# 09_Misc.net
KiCad netlist of a schematic drawn in Altium Designer
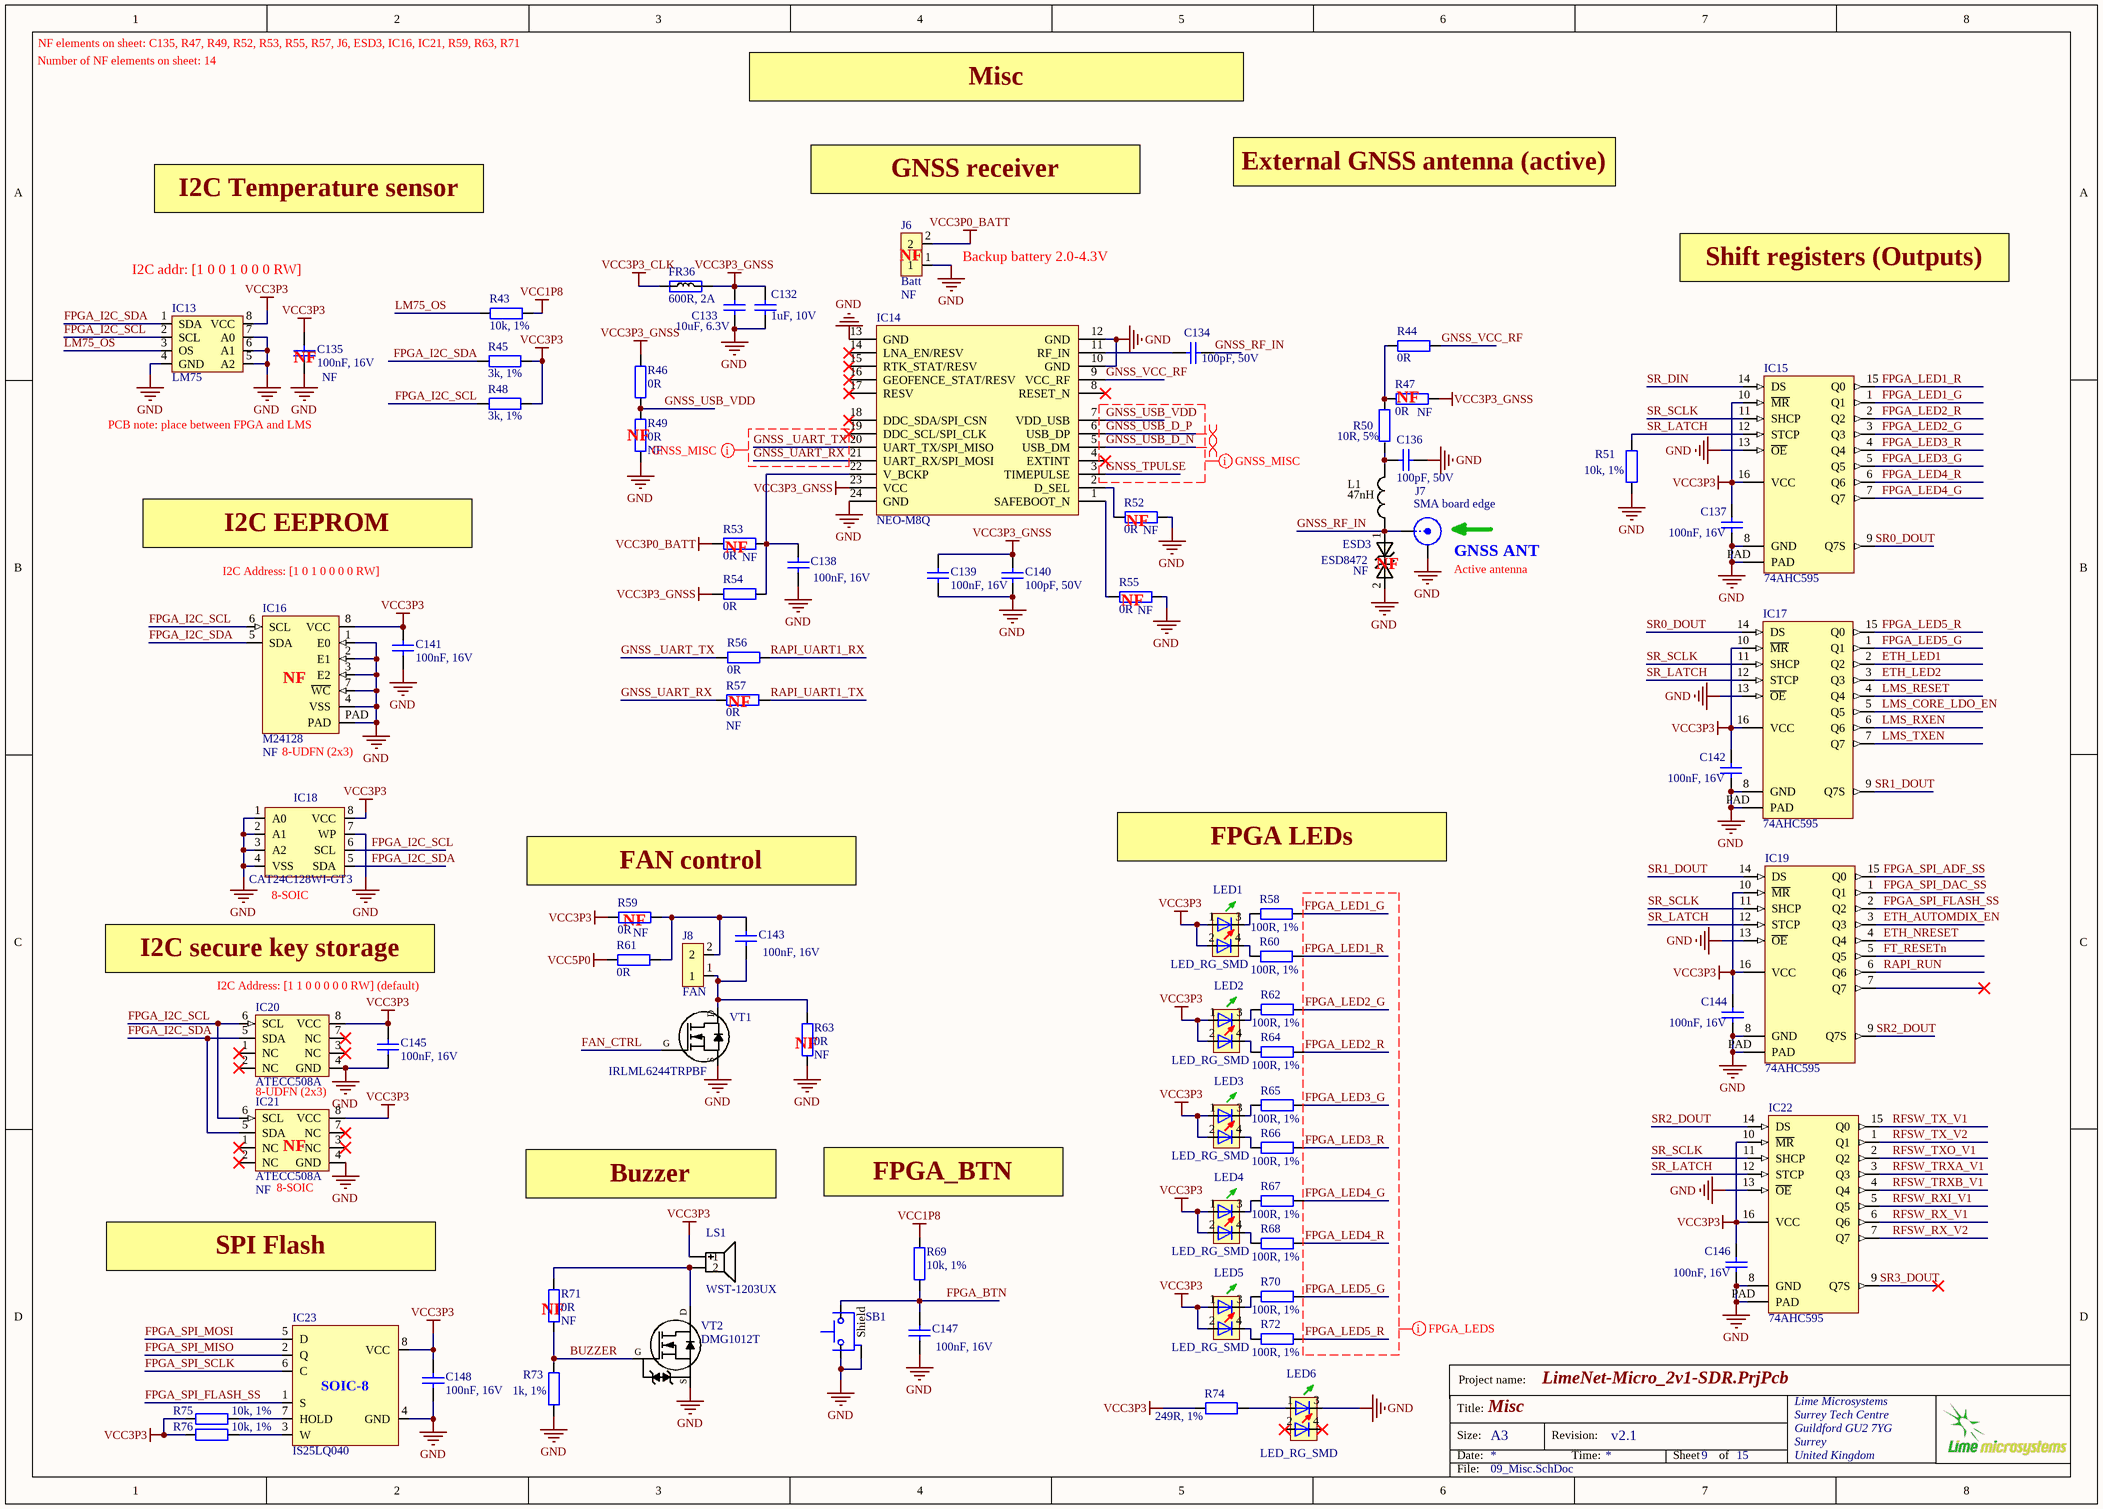
[diagram p0: 09_Misc.SchDoc]

(export (version "E")
  (design (tool "Eeschema 10.0.6"))
  (components
    (comp (ref "C132")
      (value "1uF, 10V")
      (footprint "CAP0402")
      (description "CAP CER 1UF 10V X5R 0402")
      (fields (field (name "MANUFACTURER") "Yageo") (field (name "TOLERANCE") "±20%"))
      (libsource (lib "LimeMicroAltiumLib_schLib") (part "Cap_0402"))
    )
    (comp (ref "C133")
      (value "10uF, 6.3V")
      (footprint "CAP0603")
      (fields (field (name "TOLERANCE") "±20%") (field (name "MANUFACTURER") "Yageo"))
      (libsource (lib "LimeFPGAboard_schLib") (part "Cap_0603"))
    )
    (comp (ref "C134")
      (value "100pF, 50V")
      (footprint "CAP0402")
      (fields (field (name "TOLERANCE") "±5%") (field (name "MANUFACTURER") "Yageo"))
      (libsource (lib "LimeMicroAltiumLib_schLib") (part "Cap_0402"))
    )
    (comp (ref "C135")
      (value "100nF, 16V")
      (footprint "CAP0402")
      (fields
        (field (name "TOLERANCE") "10 %")
        (field (name "MANUFACTURER") "Murata Electronics")
        (field (name "MANUFACTURER PART NUMBER") "GRM155R71C104KA88D")
        (field (name "ASSEMBLY INFO") "NF")
      )
      (libsource (lib "LimeFPGAboard_schLib") (part "Cap_0603"))
    )
    (comp (ref "C136")
      (value "100pF, 50V")
      (footprint "CAP0402")
      (fields (field (name "TOLERANCE") "±5%") (field (name "MANUFACTURER") "Yageo"))
      (libsource (lib "LimeMicroAltiumLib_schLib") (part "Cap_0402"))
    )
    (comp (ref "C137")
      (value "100nF, 16V")
      (footprint "CAP0402")
      (fields
        (field (name "MANUFACTURER") "Murata Electronics")
        (field (name "TOLERANCE") "10 %")
        (field (name "MANUFACTURER PART NUMBER") "GRM155R71C104KA88D")
      )
      (libsource (lib "LimeMicroAltiumLib_schLib") (part "Cap_0402"))
    )
    (comp (ref "C138")
      (value "100nF, 16V")
      (footprint "CAP0402")
      (fields
        (field (name "TOLERANCE") "10 %")
        (field (name "MANUFACTURER") "Murata Electronics")
        (field (name "MANUFACTURER PART NUMBER") "GRM155R71C104KA88D")
      )
      (libsource (lib "LimeFPGAboard_schLib") (part "Cap_0603"))
    )
    (comp (ref "C139")
      (value "100nF, 16V")
      (footprint "CAP0402")
      (fields
        (field (name "MANUFACTURER") "Murata Electronics")
        (field (name "TOLERANCE") "10 %")
        (field (name "MANUFACTURER PART NUMBER") "GRM155R71C104KA88D")
      )
      (libsource (lib "LimeMicroAltiumLib_schLib") (part "Cap_0402"))
    )
    (comp (ref "C140")
      (value "100pF, 50V")
      (footprint "CAP0402")
      (fields (field (name "TOLERANCE") "±5%") (field (name "MANUFACTURER") "Yageo"))
      (libsource (lib "LimeMicroAltiumLib_schLib") (part "Cap_0402"))
    )
    (comp (ref "C141")
      (value "100nF, 16V")
      (footprint "CAP0402")
      (fields
        (field (name "TOLERANCE") "10 %")
        (field (name "MANUFACTURER") "Murata Electronics")
        (field (name "MANUFACTURER PART NUMBER") "GRM155R71C104KA88D")
      )
      (libsource (lib "LimeFPGAboard_schLib") (part "Cap_0603"))
    )
    (comp (ref "C142")
      (value "100nF, 16V")
      (footprint "CAP0402")
      (fields
        (field (name "MANUFACTURER") "Murata Electronics")
        (field (name "TOLERANCE") "10 %")
        (field (name "MANUFACTURER PART NUMBER") "GRM155R71C104KA88D")
      )
      (libsource (lib "LimeMicroAltiumLib_schLib") (part "Cap_0402"))
    )
    (comp (ref "C143")
      (value "100nF, 16V")
      (footprint "CAP0402")
      (fields
        (field (name "TOLERANCE") "10 %")
        (field (name "MANUFACTURER") "Murata Electronics")
        (field (name "MANUFACTURER PART NUMBER") "GRM155R71C104KA88D")
      )
      (libsource (lib "LimeFPGAboard_schLib") (part "Cap_0603"))
    )
    (comp (ref "C144")
      (value "100nF, 16V")
      (footprint "CAP0402")
      (fields
        (field (name "MANUFACTURER") "Murata Electronics")
        (field (name "TOLERANCE") "10 %")
        (field (name "MANUFACTURER PART NUMBER") "GRM155R71C104KA88D")
      )
      (libsource (lib "LimeMicroAltiumLib_schLib") (part "Cap_0402"))
    )
    (comp (ref "C145")
      (value "100nF, 16V")
      (footprint "CAP0402")
      (fields
        (field (name "TOLERANCE") "10 %")
        (field (name "MANUFACTURER") "Murata Electronics")
        (field (name "MANUFACTURER PART NUMBER") "GRM155R71C104KA88D")
      )
      (libsource (lib "LimeFPGAboard_schLib") (part "Cap_0603"))
    )
    (comp (ref "C146")
      (value "100nF, 16V")
      (footprint "CAP0402")
      (fields
        (field (name "MANUFACTURER") "Murata Electronics")
        (field (name "TOLERANCE") "10 %")
        (field (name "MANUFACTURER PART NUMBER") "GRM155R71C104KA88D")
      )
      (libsource (lib "LimeMicroAltiumLib_schLib") (part "Cap_0402"))
    )
    (comp (ref "C147")
      (value "100nF, 16V")
      (footprint "CAP0402")
      (fields
        (field (name "TOLERANCE") "10 %")
        (field (name "MANUFACTURER") "Murata Electronics")
        (field (name "MANUFACTURER PART NUMBER") "GRM155R71C104KA88D")
      )
      (libsource (lib "LimeFPGAboard_schLib") (part "Cap_0603"))
    )
    (comp (ref "C148")
      (value "100nF, 16V")
      (footprint "CAP0402")
      (fields
        (field (name "TOLERANCE") "10 %")
        (field (name "MANUFACTURER") "Murata Electronics")
        (field (name "MANUFACTURER PART NUMBER") "GRM155R71C104KA88D")
      )
      (libsource (lib "LimeFPGAboard_schLib") (part "Cap_0603"))
    )
    (comp (ref "ESD3")
      (value "ESD8472")
      (footprint "ESD8472_X3DFN2")
      (fields (field (name "MANUFACTURER") "ON Semiconductor") (field (name "ASSEMBLY INFO") "NF"))
      (libsource (lib "LimeMicroAltiumLib_schLib") (part "ESD8472"))
    )
    (comp (ref "FR36")
      (value "600R, 2A")
      (footprint "RES0805")
      (fields (field (name "MANUFACTURER") "TDK Corporation"))
      (libsource (lib "LimeFPGAboard_schLib") (part "Ferrite"))
    )
    (comp (ref "IC13")
      (value "LM75")
      (footprint "HWSON8_LM75")
      (fields (field (name "MANUFACTURER") "NXP Semiconductors"))
      (libsource (lib "LimeMicroAltiumLib_schLib") (part "LM75"))
    )
    (comp (ref "IC14")
      (value "NEO-M8Q")
      (footprint "NEO-7M/8M")
      (description "GNSS engine for GPS/QZSS, GLONASS")
      (fields (field (name "MANUFACTURER") "u-blox") (field (name "MANUFACTURER PART NUMBER") "NEO-M8Q-0"))
      (libsource (lib "LimeMicroAltiumLib_schLib") (part "NEO-M8P_M8M"))
    )
    (comp (ref "IC15")
      (value "74AHC595")
      (footprint "74HC595BQ,115")
      (fields (field (name "MANUFACTURER") "Nexperia USA Inc."))
      (libsource (lib "LimeMicroAltiumLib_schLib") (part "74HC595BQ,115"))
    )
    (comp (ref "IC16")
      (value "M24128")
      (footprint "M24128-DFMC6TG")
      (fields (field (name "MANUFACTURER") "STMicroelectronics") (field (name "ASSEMBLY INFO") "NF"))
      (libsource (lib "LimeMicroAltiumLib_schLib") (part "M24128-DFMC6TG"))
    )
    (comp (ref "IC17")
      (value "74AHC595")
      (footprint "74HC595BQ,115")
      (fields (field (name "MANUFACTURER") "Nexperia USA Inc."))
      (libsource (lib "LimeMicroAltiumLib_schLib") (part "74HC595BQ,115"))
    )
    (comp (ref "IC18")
      (value "CAT24C128WI-GT3")
      (footprint "SOIC127P600-8DL_v2")
      (fields (field (name "MANUFACTURER") "ON Semiconductor") (field (name "BASE PART NUMBER") "CAT24C128"))
      (libsource (lib "LimeMicroAltiumLib_schLib") (part "24FC64F"))
    )
    (comp (ref "IC19")
      (value "74AHC595")
      (footprint "74HC595BQ,115")
      (fields (field (name "MANUFACTURER") "Nexperia USA Inc."))
      (libsource (lib "LimeMicroAltiumLib_schLib") (part "74HC595BQ,115"))
    )
    (comp (ref "IC20")
      (value "ATECC508A")
      (footprint "ATECC508A_UDFN8")
      (fields (field (name "MANUFACTURER") "Microchip"))
      (libsource (lib "LimeMicroAltiumLib_schLib_r01") (part "ATECC508A_authentication_IC"))
    )
    (comp (ref "IC21")
      (value "ATECC508A")
      (footprint "SOIC127P600-8DL_v2")
      (fields
        (field (name "ASSEMBLY INFO") "NF")
        (field (name "MANUFACTURER") "Microchip Technology")
        (field (name "BASE PART NUMBER") "ATECC508")
      )
      (libsource (lib "LimeMicroAltiumLib_schLib_r01") (part "ATECC508A_authentication_IC"))
    )
    (comp (ref "IC22")
      (value "74AHC595")
      (footprint "74HC595BQ,115")
      (fields (field (name "MANUFACTURER") "Nexperia USA Inc."))
      (libsource (lib "LimeMicroAltiumLib_schLib") (part "74HC595BQ,115"))
    )
    (comp (ref "IC23")
      (value "IS25LQ040")
      (footprint "M25P40-VMN6TPB_SO8N")
      (fields (field (name "MANUFACTURER") "ISSI, Integrated Silicon Solution Inc"))
      (libsource (lib "LimeFPGAboard_schLib") (part "M25P40"))
    )
    (comp (ref "J6")
      (value "Batt")
      (footprint "HDR_1x2")
      (fields (field (name "ASSEMBLY INFO") "NF") (field (name "MANUFACTURER") "3M"))
      (libsource (lib "LimeFPGAboard_schLib") (part "Jumper"))
    )
    (comp (ref "J7")
      (value "SMA board edge")
      (footprint "SMA_connector_board_edge_SM")
      (description "CONN SMA JACK STR 50OHM EDGE MNT")
      (fields (field (name "MANUFACTURER") "RF Solutions"))
      (libsource (lib "LimeMicroAltiumLib_schLib") (part "RF_IF_connector"))
    )
    (comp (ref "J8")
      (value "FAN")
      (footprint "HDR_1x2")
      (fields (field (name "MANUFACTURER") "3M"))
      (libsource (lib "LimeFPGAboard_schLib") (part "Jumper"))
    )
    (comp (ref "L1")
      (value "47nH")
      (footprint "RES0402")
      (fields
        (field (name "MANUFACTURER") "COILCRAFT")
        (field (name "MANUFACTURER PART NUMBER") "0402HP-47NXJLU")
      )
      (libsource (lib "LimeMicroAltiumLib_schLib") (part "Inductor_0603"))
    )
    (comp (ref "LED1")
      (value "LED_RG_SMD")
      (footprint "LED-2x0603")
      (fields (field (name "MANUFACTURER") "Avago Technologies US Inc."))
      (libsource (lib "LimeMicroAltiumLib_schLib") (part "LED_green_red_SMD"))
    )
    (comp (ref "LED2")
      (value "LED_RG_SMD")
      (footprint "LED-2x0603")
      (fields (field (name "MANUFACTURER") "Avago Technologies US Inc."))
      (libsource (lib "LimeMicroAltiumLib_schLib") (part "LED_green_red_SMD"))
    )
    (comp (ref "LED3")
      (value "LED_RG_SMD")
      (footprint "LED-2x0603")
      (fields (field (name "MANUFACTURER") "Avago Technologies US Inc."))
      (libsource (lib "LimeMicroAltiumLib_schLib") (part "LED_green_red_SMD"))
    )
    (comp (ref "LED4")
      (value "LED_RG_SMD")
      (footprint "LED-2x0603")
      (fields (field (name "MANUFACTURER") "Avago Technologies US Inc."))
      (libsource (lib "LimeMicroAltiumLib_schLib") (part "LED_green_red_SMD"))
    )
    (comp (ref "LED5")
      (value "LED_RG_SMD")
      (footprint "LED-2x0603")
      (fields (field (name "MANUFACTURER") "Avago Technologies US Inc."))
      (libsource (lib "LimeMicroAltiumLib_schLib") (part "LED_green_red_SMD"))
    )
    (comp (ref "LED6")
      (value "LED_RG_SMD")
      (footprint "LED-2x0603")
      (fields (field (name "MANUFACTURER") "Avago Technologies US Inc."))
      (libsource (lib "LimeMicroAltiumLib_schLib") (part "LED_green_red_SMD"))
    )
    (comp (ref "LS1")
      (value "WST-1203UX")
      (footprint "BUZZER_WST-1203UX")
      (fields (field (name "MANUFACTURER") "Soberton Inc."))
      (libsource (lib "LimeMicroAltiumLib_schLib_r01") (part "BUZZER_WST-1203UX"))
    )
    (comp (ref "R43")
      (value "10k, 1%")
      (footprint "RES0402")
      (fields (field (name "MANUFACTURER") "Yageo") (field (name "TOLERANCE") "±1%"))
      (libsource (lib "LimeMicroAltiumLib_schLib") (part "Res_0402"))
    )
    (comp (ref "R44")
      (value "0R")
      (footprint "RES0402")
      (fields (field (name "MANUFACTURER") "Yageo") (field (name "TOLERANCE") "Jumper"))
      (libsource (lib "LimeMicroAltiumLib_schLib") (part "Res_0402"))
    )
    (comp (ref "R45")
      (value "3k, 1%")
      (footprint "RES0402")
      (fields (field (name "TOLERANCE") "±1%") (field (name "MANUFACTURER") "Vishay Dale"))
      (libsource (lib "LimeMicroAltiumLib_schLib") (part "Res_0402"))
    )
    (comp (ref "R46")
      (value "0R")
      (footprint "RES0402")
      (fields (field (name "MANUFACTURER") "Yageo") (field (name "TOLERANCE") "Jumper"))
      (libsource (lib "LimeMicroAltiumLib_schLib") (part "Res_0402"))
    )
    (comp (ref "R47")
      (value "0R")
      (footprint "RES0402")
      (fields
        (field (name "ASSEMBLY INFO") "NF")
        (field (name "MANUFACTURER") "Yageo")
        (field (name "TOLERANCE") "Jumper")
      )
      (libsource (lib "LimeMicroAltiumLib_schLib") (part "Res_0402"))
    )
    (comp (ref "R48")
      (value "3k, 1%")
      (footprint "RES0402")
      (fields (field (name "TOLERANCE") "±1%") (field (name "MANUFACTURER") "Vishay Dale"))
      (libsource (lib "LimeMicroAltiumLib_schLib") (part "Res_0402"))
    )
    (comp (ref "R49")
      (value "0R")
      (footprint "RES0402")
      (fields
        (field (name "ASSEMBLY INFO") "NF")
        (field (name "MANUFACTURER") "Yageo")
        (field (name "TOLERANCE") "Jumper")
      )
      (libsource (lib "LimeMicroAltiumLib_schLib") (part "Res_0402"))
    )
    (comp (ref "R50")
      (value "10R, 5%")
      (footprint "RES0402")
      (fields (field (name "TOLERANCE") "±5%") (field (name "MANUFACTURER") "Yageo"))
      (libsource (lib "LimeMicroAltiumLib_schLib") (part "Res_0402"))
    )
    (comp (ref "R51")
      (value "10k, 1%")
      (footprint "RES0402")
      (fields (field (name "MANUFACTURER") "Yageo") (field (name "TOLERANCE") "±1%"))
      (libsource (lib "LimeMicroAltiumLib_schLib") (part "Res_0402"))
    )
    (comp (ref "R52")
      (value "0R")
      (footprint "RES0402")
      (fields
        (field (name "ASSEMBLY INFO") "NF")
        (field (name "MANUFACTURER") "Yageo")
        (field (name "TOLERANCE") "Jumper")
      )
      (libsource (lib "LimeMicroAltiumLib_schLib") (part "Res_0402"))
    )
    (comp (ref "R53")
      (value "0R")
      (footprint "RES0402")
      (fields
        (field (name "ASSEMBLY INFO") "NF")
        (field (name "MANUFACTURER") "Yageo")
        (field (name "TOLERANCE") "Jumper")
      )
      (libsource (lib "LimeMicroAltiumLib_schLib") (part "Res_0402"))
    )
    (comp (ref "R54")
      (value "0R")
      (footprint "RES0402")
      (fields (field (name "MANUFACTURER") "Yageo") (field (name "TOLERANCE") "Jumper"))
      (libsource (lib "LimeMicroAltiumLib_schLib") (part "Res_0402"))
    )
    (comp (ref "R55")
      (value "0R")
      (footprint "RES0402")
      (fields
        (field (name "ASSEMBLY INFO") "NF")
        (field (name "MANUFACTURER") "Yageo")
        (field (name "TOLERANCE") "Jumper")
      )
      (libsource (lib "LimeMicroAltiumLib_schLib") (part "Res_0402"))
    )
    (comp (ref "R56")
      (value "0R")
      (footprint "RES0402")
      (fields (field (name "MANUFACTURER") "Yageo") (field (name "TOLERANCE") "Jumper"))
      (libsource (lib "LimeMicroAltiumLib_schLib") (part "Res_0402"))
    )
    (comp (ref "R57")
      (value "0R")
      (footprint "RES0402")
      (fields
        (field (name "ASSEMBLY INFO") "NF")
        (field (name "MANUFACTURER") "Yageo")
        (field (name "TOLERANCE") "Jumper")
      )
      (libsource (lib "LimeMicroAltiumLib_schLib") (part "Res_0402"))
    )
    (comp (ref "R58")
      (value "100R, 1%")
      (footprint "RES0402")
      (fields (field (name "TOLERANCE") "±1%") (field (name "MANUFACTURER") "Stackpole Electronics Inc."))
      (libsource (lib "LimeMicroAltiumLib_schLib") (part "Res_0402"))
    )
    (comp (ref "R59")
      (value "0R")
      (footprint "RES0402")
      (fields
        (field (name "ASSEMBLY INFO") "NF")
        (field (name "MANUFACTURER") "Yageo")
        (field (name "TOLERANCE") "Jumper")
      )
      (libsource (lib "LimeMicroAltiumLib_schLib") (part "Res_0402"))
    )
    (comp (ref "R60")
      (value "100R, 1%")
      (footprint "RES0402")
      (fields (field (name "TOLERANCE") "±1%") (field (name "MANUFACTURER") "Stackpole Electronics Inc."))
      (libsource (lib "LimeMicroAltiumLib_schLib") (part "Res_0402"))
    )
    (comp (ref "R61")
      (value "0R")
      (footprint "RES0402")
      (fields (field (name "MANUFACTURER") "Yageo") (field (name "TOLERANCE") "Jumper"))
      (libsource (lib "LimeMicroAltiumLib_schLib") (part "Res_0402"))
    )
    (comp (ref "R62")
      (value "100R, 1%")
      (footprint "RES0402")
      (fields (field (name "TOLERANCE") "±1%") (field (name "MANUFACTURER") "Stackpole Electronics Inc."))
      (libsource (lib "LimeMicroAltiumLib_schLib") (part "Res_0402"))
    )
    (comp (ref "R63")
      (value "0R")
      (footprint "RES0402")
      (fields
        (field (name "ASSEMBLY INFO") "NF")
        (field (name "MANUFACTURER") "Yageo")
        (field (name "TOLERANCE") "Jumper")
      )
      (libsource (lib "LimeMicroAltiumLib_schLib") (part "Res_0402"))
    )
    (comp (ref "R64")
      (value "100R, 1%")
      (footprint "RES0402")
      (fields (field (name "TOLERANCE") "±1%") (field (name "MANUFACTURER") "Stackpole Electronics Inc."))
      (libsource (lib "LimeMicroAltiumLib_schLib") (part "Res_0402"))
    )
    (comp (ref "R65")
      (value "100R, 1%")
      (footprint "RES0402")
      (fields (field (name "TOLERANCE") "±1%") (field (name "MANUFACTURER") "Stackpole Electronics Inc."))
      (libsource (lib "LimeMicroAltiumLib_schLib") (part "Res_0402"))
    )
    (comp (ref "R66")
      (value "100R, 1%")
      (footprint "RES0402")
      (fields (field (name "TOLERANCE") "±1%") (field (name "MANUFACTURER") "Stackpole Electronics Inc."))
      (libsource (lib "LimeMicroAltiumLib_schLib") (part "Res_0402"))
    )
    (comp (ref "R67")
      (value "100R, 1%")
      (footprint "RES0402")
      (fields (field (name "TOLERANCE") "±1%") (field (name "MANUFACTURER") "Stackpole Electronics Inc."))
      (libsource (lib "LimeMicroAltiumLib_schLib") (part "Res_0402"))
    )
    (comp (ref "R68")
      (value "100R, 1%")
      (footprint "RES0402")
      (fields (field (name "TOLERANCE") "±1%") (field (name "MANUFACTURER") "Stackpole Electronics Inc."))
      (libsource (lib "LimeMicroAltiumLib_schLib") (part "Res_0402"))
    )
    (comp (ref "R69")
      (value "10k, 1%")
      (footprint "RES0402")
      (fields (field (name "MANUFACTURER") "Yageo") (field (name "TOLERANCE") "±1%"))
      (libsource (lib "LimeMicroAltiumLib_schLib") (part "Res_0402"))
    )
    (comp (ref "R70")
      (value "100R, 1%")
      (footprint "RES0402")
      (fields (field (name "TOLERANCE") "±1%") (field (name "MANUFACTURER") "Stackpole Electronics Inc."))
      (libsource (lib "LimeMicroAltiumLib_schLib") (part "Res_0402"))
    )
    (comp (ref "R71")
      (value "0R")
      (footprint "RES0402")
      (fields
        (field (name "ASSEMBLY INFO") "NF")
        (field (name "MANUFACTURER") "Yageo")
        (field (name "TOLERANCE") "Jumper")
      )
      (libsource (lib "LimeMicroAltiumLib_schLib") (part "Res_0402"))
    )
    (comp (ref "R72")
      (value "100R, 1%")
      (footprint "RES0402")
      (fields (field (name "TOLERANCE") "±1%") (field (name "MANUFACTURER") "Stackpole Electronics Inc."))
      (libsource (lib "LimeMicroAltiumLib_schLib") (part "Res_0402"))
    )
    (comp (ref "R73")
      (value "1k, 1%")
      (footprint "RES0402")
      (fields (field (name "MANUFACTURER") "Stackpole Electronics Inc") (field (name "TOLERANCE") "±1%"))
      (libsource (lib "LimeMicroAltiumLib_schLib") (part "Res_0402"))
    )
    (comp (ref "R74")
      (value "249R, 1%")
      (footprint "RES0402")
      (fields (field (name "MANUFACTURER") "Stackpole Electronics Inc") (field (name "TOLERANCE") "±1%"))
      (libsource (lib "LimeMicroAltiumLib_schLib") (part "Res_0402"))
    )
    (comp (ref "R75")
      (value "10k, 1%")
      (footprint "RES0402")
      (fields (field (name "MANUFACTURER") "Yageo") (field (name "TOLERANCE") "±1%"))
      (libsource (lib "LimeMicroAltiumLib_schLib") (part "Res_0402"))
    )
    (comp (ref "R76")
      (value "10k, 1%")
      (footprint "RES0402")
      (fields (field (name "MANUFACTURER") "Yageo") (field (name "TOLERANCE") "±1%"))
      (libsource (lib "LimeMicroAltiumLib_schLib") (part "Res_0402"))
    )
    (comp (ref "SB1")
      (value "Switch tactile right edge")
      (footprint "SW_TACTILE_RIGHT_EDGE")
      (fields (field (name "MANUFACTURER") "TE Connectivity ALCOSWITCH Switches"))
      (libsource (lib "LimeMicroAltiumLib_schLib_r01") (part "Button_right_edge"))
    )
    (comp (ref "VT1")
      (value "IRLML6244TRPBF")
      (footprint "SOT23-3")
      (description "NDS331N")
      (fields (field (name "MANUFACTURER") "Infineon Technologies"))
      (libsource (lib "LimeFPGAboard_schLib") (part "NDS331N"))
    )
    (comp (ref "VT2")
      (value "DMG1012T")
      (footprint "SOT523")
      (fields (field (name "MANUFACTURER") "Diodes Incorporated"))
      (libsource (lib "LimeMicroAltiumLib_schLib_r01") (part "DMG1012T"))
    )
  )
  (nets
    (net (code "1") (name "/BUZZER") (class "Default")
      (node (ref "R71") (pin "1") (pinfunction "1_1") (pintype "passive"))
      (node (ref "R73") (pin "1") (pinfunction "1_1") (pintype "passive"))
      (node (ref "VT2") (pin "G") (pinfunction "G_G") (pintype "passive"))
    )
    (net (code "2") (name "/ETH_AUTOMDIX_EN") (class "Default")
      (node (ref "IC19") (pin "3") (pinfunction "Q3_3") (pintype "output"))
    )
    (net (code "3") (name "/ETH_LED1") (class "Default")
      (node (ref "IC17") (pin "2") (pinfunction "Q2_2") (pintype "output"))
    )
    (net (code "4") (name "/ETH_LED2") (class "Default")
      (node (ref "IC17") (pin "3") (pinfunction "Q3_3") (pintype "output"))
    )
    (net (code "5") (name "/ETH_NRESET") (class "Default")
      (node (ref "IC19") (pin "4") (pinfunction "Q4_4") (pintype "output"))
    )
    (net (code "6") (name "/FAN_CTRL") (class "Default")
      (node (ref "VT1") (pin "G") (pinfunction "G_G") (pintype "passive"))
    )
    (net (code "7") (name "/FPGA_BTN") (class "Default")
      (node (ref "C147") (pin "1") (pinfunction "1_1") (pintype "passive"))
      (node (ref "R69") (pin "2") (pinfunction "2_2") (pintype "passive"))
      (node (ref "SB1") (pin "1") (pinfunction "1_1") (pintype "passive"))
    )
    (net (code "8") (name "/FPGA_I2C_SCL") (class "Default")
      (node (ref "IC13") (pin "2") (pinfunction "SCL_2") (pintype "passive"))
      (node (ref "IC16") (pin "6") (pinfunction "SCL_6") (pintype "input"))
      (node (ref "IC18") (pin "6") (pinfunction "SCL_6") (pintype "passive"))
      (node (ref "IC20") (pin "6") (pinfunction "SCL_6") (pintype "input"))
      (node (ref "IC21") (pin "6") (pinfunction "SCL_6") (pintype "input"))
      (node (ref "R48") (pin "2") (pinfunction "2_2") (pintype "passive"))
    )
    (net (code "9") (name "/FPGA_I2C_SDA") (class "Default")
      (node (ref "IC13") (pin "1") (pinfunction "SDA_1") (pintype "passive"))
      (node (ref "IC16") (pin "5") (pinfunction "SDA_5") (pintype "bidirectional"))
      (node (ref "IC18") (pin "5") (pinfunction "SDA_5") (pintype "passive"))
      (node (ref "IC20") (pin "5") (pinfunction "SDA_5") (pintype "bidirectional"))
      (node (ref "IC21") (pin "5") (pinfunction "SDA_5") (pintype "bidirectional"))
      (node (ref "R45") (pin "2") (pinfunction "2_2") (pintype "passive"))
    )
    (net (code "10") (name "/FPGA_LED1_G") (class "Default")
      (node (ref "IC15") (pin "1") (pinfunction "Q1_1") (pintype "output"))
      (node (ref "R58") (pin "2") (pinfunction "2_2") (pintype "passive"))
    )
    (net (code "11") (name "/FPGA_LED1_R") (class "Default")
      (node (ref "IC15") (pin "15") (pinfunction "Q0_15") (pintype "output"))
      (node (ref "R60") (pin "2") (pinfunction "2_2") (pintype "passive"))
    )
    (net (code "12") (name "/FPGA_LED2_G") (class "Default")
      (node (ref "IC15") (pin "3") (pinfunction "Q3_3") (pintype "output"))
      (node (ref "R62") (pin "2") (pinfunction "2_2") (pintype "passive"))
    )
    (net (code "13") (name "/FPGA_LED2_R") (class "Default")
      (node (ref "IC15") (pin "2") (pinfunction "Q2_2") (pintype "output"))
      (node (ref "R64") (pin "2") (pinfunction "2_2") (pintype "passive"))
    )
    (net (code "14") (name "/FPGA_LED3_G") (class "Default")
      (node (ref "IC15") (pin "5") (pinfunction "Q5_5") (pintype "output"))
      (node (ref "R65") (pin "2") (pinfunction "2_2") (pintype "passive"))
    )
    (net (code "15") (name "/FPGA_LED3_R") (class "Default")
      (node (ref "IC15") (pin "4") (pinfunction "Q4_4") (pintype "output"))
      (node (ref "R66") (pin "2") (pinfunction "2_2") (pintype "passive"))
    )
    (net (code "16") (name "/FPGA_LED4_G") (class "Default")
      (node (ref "IC15") (pin "7") (pinfunction "Q7_7") (pintype "output"))
      (node (ref "R67") (pin "2") (pinfunction "2_2") (pintype "passive"))
    )
    (net (code "17") (name "/FPGA_LED4_R") (class "Default")
      (node (ref "IC15") (pin "6") (pinfunction "Q6_6") (pintype "output"))
      (node (ref "R68") (pin "2") (pinfunction "2_2") (pintype "passive"))
    )
    (net (code "18") (name "/FPGA_LED5_G") (class "Default")
      (node (ref "IC17") (pin "1") (pinfunction "Q1_1") (pintype "output"))
      (node (ref "R70") (pin "2") (pinfunction "2_2") (pintype "passive"))
    )
    (net (code "19") (name "/FPGA_LED5_R") (class "Default")
      (node (ref "IC17") (pin "15") (pinfunction "Q0_15") (pintype "output"))
      (node (ref "R72") (pin "2") (pinfunction "2_2") (pintype "passive"))
    )
    (net (code "20") (name "/FPGA_SPI_ADF_SS") (class "Default")
      (node (ref "IC19") (pin "15") (pinfunction "Q0_15") (pintype "output"))
    )
    (net (code "21") (name "/FPGA_SPI_DAC_SS") (class "Default")
      (node (ref "IC19") (pin "1") (pinfunction "Q1_1") (pintype "output"))
    )
    (net (code "22") (name "/FPGA_SPI_FLASH_SS") (class "Default")
      (node (ref "IC19") (pin "2") (pinfunction "Q2_2") (pintype "output"))
      (node (ref "IC23") (pin "1") (pinfunction "S_1") (pintype "passive"))
    )
    (net (code "23") (name "/FPGA_SPI_MISO") (class "Default")
      (node (ref "IC23") (pin "2") (pinfunction "Q_2") (pintype "passive"))
    )
    (net (code "24") (name "/FPGA_SPI_MOSI") (class "Default")
      (node (ref "IC23") (pin "5") (pinfunction "D_5") (pintype "passive"))
    )
    (net (code "25") (name "/FPGA_SPI_SCLK") (class "Default")
      (node (ref "IC23") (pin "6") (pinfunction "C_6") (pintype "passive"))
    )
    (net (code "26") (name "/FT_RESETn") (class "Default")
      (node (ref "IC19") (pin "5") (pinfunction "Q5_5") (pintype "output"))
    )
    (net (code "27") (name "/GNSS _UART_TX") (class "Default")
      (node (ref "IC14") (pin "20") (pinfunction "UART_TX/SPI_MISO_20") (pintype "passive"))
      (node (ref "R56") (pin "2") (pinfunction "2_2") (pintype "passive"))
    )
    (net (code "28") (name "/GNSS_RF_IN") (class "Default")
      (node (ref "C134") (pin "1") (pinfunction "1_1") (pintype "passive"))
      (node (ref "ESD3") (pin "1") (pinfunction "1_1") (pintype "passive"))
      (node (ref "J7") (pin "1") (pinfunction "X_1") (pintype "passive"))
      (node (ref "L1") (pin "1") (pinfunction "1_1") (pintype "passive"))
    )
    (net (code "29") (name "/GNSS_TPULSE") (class "Default")
      (node (ref "IC14") (pin "3") (pinfunction "TIMEPULSE_3") (pintype "passive"))
    )
    (net (code "30") (name "/GNSS_UART_RX") (class "Default")
      (node (ref "IC14") (pin "21") (pinfunction "UART_RX/SPI_MOSI_21") (pintype "passive"))
      (node (ref "R57") (pin "1") (pinfunction "1_1") (pintype "passive"))
    )
    (net (code "31") (name "/GNSS_USB_D_N") (class "Default")
      (node (ref "IC14") (pin "5") (pinfunction "USB_DM_5") (pintype "passive"))
    )
    (net (code "32") (name "/GNSS_USB_D_P") (class "Default")
      (node (ref "IC14") (pin "6") (pinfunction "USB_DP_6") (pintype "passive"))
    )
    (net (code "33") (name "/GNSS_USB_VDD") (class "Default")
      (node (ref "IC14") (pin "7") (pinfunction "VDD_USB_7") (pintype "passive"))
      (node (ref "R46") (pin "1") (pinfunction "1_1") (pintype "passive"))
      (node (ref "R49") (pin "1") (pinfunction "1_1") (pintype "passive"))
    )
    (net (code "34") (name "/GNSS_VCC_RF") (class "Default")
      (node (ref "IC14") (pin "9") (pinfunction "VCC_RF_9") (pintype "passive"))
      (node (ref "R44") (pin "2") (pinfunction "2_2") (pintype "passive"))
    )
    (net (code "35") (name "/LM75_OS") (class "Default")
      (node (ref "IC13") (pin "3") (pinfunction "OS_3") (pintype "passive"))
      (node (ref "R43") (pin "1") (pinfunction "1_1") (pintype "passive"))
    )
    (net (code "36") (name "/LMS_CORE_LDO_EN") (class "Default")
      (node (ref "IC17") (pin "5") (pinfunction "Q5_5") (pintype "output"))
    )
    (net (code "37") (name "/LMS_RESET") (class "Default")
      (node (ref "IC17") (pin "4") (pinfunction "Q4_4") (pintype "output"))
    )
    (net (code "38") (name "/LMS_RXEN") (class "Default")
      (node (ref "IC17") (pin "6") (pinfunction "Q6_6") (pintype "output"))
    )
    (net (code "39") (name "/LMS_TXEN") (class "Default")
      (node (ref "IC17") (pin "7") (pinfunction "Q7_7") (pintype "output"))
    )
    (net (code "40") (name "/RAPI_RUN") (class "Default")
      (node (ref "IC19") (pin "6") (pinfunction "Q6_6") (pintype "output"))
    )
    (net (code "41") (name "/RAPI_UART1_RX") (class "Default")
      (node (ref "R56") (pin "1") (pinfunction "1_1") (pintype "passive"))
    )
    (net (code "42") (name "/RAPI_UART1_TX") (class "Default")
      (node (ref "R57") (pin "2") (pinfunction "2_2") (pintype "passive"))
    )
    (net (code "43") (name "/RFSW_RXI_V1") (class "Default")
      (node (ref "IC22") (pin "5") (pinfunction "Q5_5") (pintype "output"))
    )
    (net (code "44") (name "/RFSW_RX_V1") (class "Default")
      (node (ref "IC22") (pin "6") (pinfunction "Q6_6") (pintype "output"))
    )
    (net (code "45") (name "/RFSW_RX_V2") (class "Default")
      (node (ref "IC22") (pin "7") (pinfunction "Q7_7") (pintype "output"))
    )
    (net (code "46") (name "/RFSW_TRXA_V1") (class "Default")
      (node (ref "IC22") (pin "3") (pinfunction "Q3_3") (pintype "output"))
    )
    (net (code "47") (name "/RFSW_TRXB_V1") (class "Default")
      (node (ref "IC22") (pin "4") (pinfunction "Q4_4") (pintype "output"))
    )
    (net (code "48") (name "/RFSW_TXO_V1") (class "Default")
      (node (ref "IC22") (pin "2") (pinfunction "Q2_2") (pintype "output"))
    )
    (net (code "49") (name "/RFSW_TX_V1") (class "Default")
      (node (ref "IC22") (pin "15") (pinfunction "Q0_15") (pintype "output"))
    )
    (net (code "50") (name "/RFSW_TX_V2") (class "Default")
      (node (ref "IC22") (pin "1") (pinfunction "Q1_1") (pintype "output"))
    )
    (net (code "51") (name "/SR0_DOUT") (class "Default")
      (node (ref "IC15") (pin "9") (pinfunction "Q7S_9") (pintype "output"))
      (node (ref "IC17") (pin "14") (pinfunction "DS_14") (pintype "input"))
    )
    (net (code "52") (name "/SR1_DOUT") (class "Default")
      (node (ref "IC17") (pin "9") (pinfunction "Q7S_9") (pintype "output"))
      (node (ref "IC19") (pin "14") (pinfunction "DS_14") (pintype "input"))
    )
    (net (code "53") (name "/SR2_DOUT") (class "Default")
      (node (ref "IC19") (pin "9") (pinfunction "Q7S_9") (pintype "output"))
      (node (ref "IC22") (pin "14") (pinfunction "DS_14") (pintype "input"))
    )
    (net (code "54") (name "/SR3_DOUT") (class "Default")
      (node (ref "IC22") (pin "9") (pinfunction "Q7S_9") (pintype "output+no_connect"))
    )
    (net (code "55") (name "/SR_DIN") (class "Default")
      (node (ref "IC15") (pin "14") (pinfunction "DS_14") (pintype "input"))
    )
    (net (code "56") (name "/SR_LATCH") (class "Default")
      (node (ref "IC15") (pin "12") (pinfunction "STCP_12") (pintype "input"))
      (node (ref "IC17") (pin "12") (pinfunction "STCP_12") (pintype "input"))
      (node (ref "IC19") (pin "12") (pinfunction "STCP_12") (pintype "input"))
      (node (ref "IC22") (pin "12") (pinfunction "STCP_12") (pintype "input"))
      (node (ref "R51") (pin "1") (pinfunction "1_1") (pintype "passive"))
    )
    (net (code "57") (name "/SR_SCLK") (class "Default")
      (node (ref "IC15") (pin "11") (pinfunction "SHCP_11") (pintype "input"))
      (node (ref "IC17") (pin "11") (pinfunction "SHCP_11") (pintype "input"))
      (node (ref "IC19") (pin "11") (pinfunction "SHCP_11") (pintype "input"))
      (node (ref "IC22") (pin "11") (pinfunction "SHCP_11") (pintype "input"))
    )
    (net (code "58") (name "GND") (class "Default")
      (node (ref "C132") (pin "1") (pinfunction "1_1") (pintype "passive"))
      (node (ref "C133") (pin "1") (pinfunction "1_1") (pintype "passive"))
      (node (ref "C135") (pin "2") (pinfunction "2_2") (pintype "passive"))
      (node (ref "C136") (pin "2") (pinfunction "2_2") (pintype "passive"))
      (node (ref "C137") (pin "1") (pinfunction "1_1") (pintype "passive"))
      (node (ref "C138") (pin "2") (pinfunction "2_2") (pintype "passive"))
      (node (ref "C139") (pin "1") (pinfunction "1_1") (pintype "passive"))
      (node (ref "C140") (pin "2") (pinfunction "2_2") (pintype "passive"))
      (node (ref "C141") (pin "2") (pinfunction "2_2") (pintype "passive"))
      (node (ref "C142") (pin "1") (pinfunction "1_1") (pintype "passive"))
      (node (ref "C144") (pin "1") (pinfunction "1_1") (pintype "passive"))
      (node (ref "C145") (pin "2") (pinfunction "2_2") (pintype "passive"))
      (node (ref "C146") (pin "1") (pinfunction "1_1") (pintype "passive"))
      (node (ref "C147") (pin "2") (pinfunction "2_2") (pintype "passive"))
      (node (ref "C148") (pin "2") (pinfunction "2_2") (pintype "passive"))
      (node (ref "ESD3") (pin "2") (pinfunction "2_2") (pintype "passive"))
      (node (ref "IC13") (pin "4") (pinfunction "GND_4") (pintype "passive"))
      (node (ref "IC13") (pin "5") (pinfunction "A2_5") (pintype "passive"))
      (node (ref "IC13") (pin "6") (pinfunction "A1_6") (pintype "passive"))
      (node (ref "IC13") (pin "7") (pinfunction "A0_7") (pintype "passive"))
      (node (ref "IC14") (pin "10") (pinfunction "GND_10") (pintype "passive"))
      (node (ref "IC14") (pin "12") (pinfunction "GND_12") (pintype "passive"))
      (node (ref "IC14") (pin "13") (pinfunction "GND_13") (pintype "passive"))
      (node (ref "IC14") (pin "24") (pinfunction "GND_24") (pintype "passive"))
      (node (ref "IC15") (pin "13") (pinfunction "~{OE}_13") (pintype "input"))
      (node (ref "IC15") (pin "8") (pinfunction "GND_8") (pintype "passive"))
      (node (ref "IC15") (pin "PAD") (pinfunction "PAD_PAD") (pintype "passive"))
      (node (ref "IC16") (pin "1") (pinfunction "E0_1") (pintype "input"))
      (node (ref "IC16") (pin "2") (pinfunction "E1_2") (pintype "input"))
      (node (ref "IC16") (pin "3") (pinfunction "E2_3") (pintype "input"))
      (node (ref "IC16") (pin "4") (pinfunction "VSS_4") (pintype "power_in"))
      (node (ref "IC16") (pin "7") (pinfunction "~{WC}_7") (pintype "input"))
      (node (ref "IC16") (pin "PAD") (pinfunction "PAD_PAD") (pintype "power_in"))
      (node (ref "IC17") (pin "13") (pinfunction "~{OE}_13") (pintype "input"))
      (node (ref "IC17") (pin "8") (pinfunction "GND_8") (pintype "passive"))
      (node (ref "IC17") (pin "PAD") (pinfunction "PAD_PAD") (pintype "passive"))
      (node (ref "IC18") (pin "1") (pinfunction "A0_1") (pintype "passive"))
      (node (ref "IC18") (pin "2") (pinfunction "A1_2") (pintype "passive"))
      (node (ref "IC18") (pin "3") (pinfunction "A2_3") (pintype "passive"))
      (node (ref "IC18") (pin "4") (pinfunction "VSS_4") (pintype "passive"))
      (node (ref "IC18") (pin "7") (pinfunction "WP_7") (pintype "passive"))
      (node (ref "IC19") (pin "13") (pinfunction "~{OE}_13") (pintype "input"))
      (node (ref "IC19") (pin "8") (pinfunction "GND_8") (pintype "passive"))
      (node (ref "IC19") (pin "PAD") (pinfunction "PAD_PAD") (pintype "passive"))
      (node (ref "IC20") (pin "4") (pinfunction "GND_4") (pintype "passive"))
      (node (ref "IC21") (pin "4") (pinfunction "GND_4") (pintype "passive"))
      (node (ref "IC22") (pin "13") (pinfunction "~{OE}_13") (pintype "input"))
      (node (ref "IC22") (pin "8") (pinfunction "GND_8") (pintype "passive"))
      (node (ref "IC22") (pin "PAD") (pinfunction "PAD_PAD") (pintype "passive"))
      (node (ref "IC23") (pin "4") (pinfunction "GND_4") (pintype "passive"))
      (node (ref "J6") (pin "1") (pinfunction "1_1") (pintype "passive"))
      (node (ref "J7") (pin "2") (pinfunction "Y_2") (pintype "passive"))
      (node (ref "LED6") (pin "3") (pinfunction "3_3") (pintype "power_in"))
      (node (ref "R49") (pin "2") (pinfunction "2_2") (pintype "passive"))
      (node (ref "R51") (pin "2") (pinfunction "2_2") (pintype "passive"))
      (node (ref "R52") (pin "1") (pinfunction "1_1") (pintype "passive"))
      (node (ref "R55") (pin "1") (pinfunction "1_1") (pintype "passive"))
      (node (ref "R63") (pin "1") (pinfunction "1_1") (pintype "passive"))
      (node (ref "R73") (pin "2") (pinfunction "2_2") (pintype "passive"))
      (node (ref "SB1") (pin "2") (pinfunction "2_2") (pintype "passive"))
      (node (ref "SB1") (pin "Shield") (pinfunction "Shield_Shield") (pintype "passive"))
      (node (ref "VT1") (pin "S") (pinfunction "S_S") (pintype "passive"))
      (node (ref "VT2") (pin "S") (pinfunction "S_S") (pintype "passive"))
    )
    (net (code "59") (name "Net-(C136-Pad1)") (class "Default")
      (node (ref "C136") (pin "1") (pinfunction "1_1") (pintype "passive"))
      (node (ref "L1") (pin "2") (pinfunction "2_2") (pintype "passive"))
      (node (ref "R50") (pin "2") (pinfunction "2_2") (pintype "passive"))
    )
    (net (code "60") (name "Net-(C143-Pad1)") (class "Default")
      (node (ref "C143") (pin "1") (pinfunction "1_1") (pintype "passive"))
      (node (ref "J8") (pin "2") (pinfunction "2_2") (pintype "passive"))
      (node (ref "R59") (pin "2") (pinfunction "2_2") (pintype "passive"))
      (node (ref "R61") (pin "2") (pinfunction "2_2") (pintype "passive"))
    )
    (net (code "61") (name "Net-(C143-Pad2)") (class "Default")
      (node (ref "C143") (pin "2") (pinfunction "2_2") (pintype "passive"))
      (node (ref "J8") (pin "1") (pinfunction "1_1") (pintype "passive"))
      (node (ref "R63") (pin "2") (pinfunction "2_2") (pintype "passive"))
      (node (ref "VT1") (pin "D") (pinfunction "D_D") (pintype "passive"))
    )
    (net (code "62") (name "Net-(IC14-D_SEL)") (class "Default")
      (node (ref "IC14") (pin "2") (pinfunction "D_SEL_2") (pintype "passive"))
      (node (ref "R52") (pin "2") (pinfunction "2_2") (pintype "passive"))
    )
    (net (code "63") (name "Net-(IC14-RF_IN)") (class "Default")
      (node (ref "C134") (pin "2") (pinfunction "2_2") (pintype "passive"))
      (node (ref "IC14") (pin "11") (pinfunction "RF_IN_11") (pintype "passive"))
    )
    (net (code "64") (name "Net-(IC14-SAFEBOOT_N)") (class "Default")
      (node (ref "IC14") (pin "1") (pinfunction "SAFEBOOT_N_1") (pintype "passive"))
      (node (ref "R55") (pin "2") (pinfunction "2_2") (pintype "passive"))
    )
    (net (code "65") (name "Net-(IC14-V_BCKP)") (class "Default")
      (node (ref "C138") (pin "1") (pinfunction "1_1") (pintype "passive"))
      (node (ref "IC14") (pin "22") (pinfunction "V_BCKP_22") (pintype "passive"))
      (node (ref "R53") (pin "1") (pinfunction "1_1") (pintype "passive"))
      (node (ref "R54") (pin "1") (pinfunction "1_1") (pintype "passive"))
    )
    (net (code "66") (name "Net-(IC23-HOLD)") (class "Default")
      (node (ref "IC23") (pin "7") (pinfunction "HOLD_7") (pintype "passive"))
      (node (ref "R75") (pin "2") (pinfunction "2_2") (pintype "passive"))
    )
    (net (code "67") (name "Net-(IC23-W)") (class "Default")
      (node (ref "IC23") (pin "3") (pinfunction "W_3") (pintype "passive"))
      (node (ref "R76") (pin "2") (pinfunction "2_2") (pintype "passive"))
    )
    (net (code "68") (name "Net-(LED1-Pad3)") (class "Default")
      (node (ref "LED1") (pin "3") (pinfunction "3_3") (pintype "power_in"))
      (node (ref "R58") (pin "1") (pinfunction "1_1") (pintype "passive"))
    )
    (net (code "69") (name "Net-(LED1-Pad4)") (class "Default")
      (node (ref "LED1") (pin "4") (pinfunction "4_4") (pintype "power_in"))
      (node (ref "R60") (pin "1") (pinfunction "1_1") (pintype "passive"))
    )
    (net (code "70") (name "Net-(LED2-Pad3)") (class "Default")
      (node (ref "LED2") (pin "3") (pinfunction "3_3") (pintype "power_in"))
      (node (ref "R62") (pin "1") (pinfunction "1_1") (pintype "passive"))
    )
    (net (code "71") (name "Net-(LED2-Pad4)") (class "Default")
      (node (ref "LED2") (pin "4") (pinfunction "4_4") (pintype "power_in"))
      (node (ref "R64") (pin "1") (pinfunction "1_1") (pintype "passive"))
    )
    (net (code "72") (name "Net-(LED3-Pad3)") (class "Default")
      (node (ref "LED3") (pin "3") (pinfunction "3_3") (pintype "power_in"))
      (node (ref "R65") (pin "1") (pinfunction "1_1") (pintype "passive"))
    )
    (net (code "73") (name "Net-(LED3-Pad4)") (class "Default")
      (node (ref "LED3") (pin "4") (pinfunction "4_4") (pintype "power_in"))
      (node (ref "R66") (pin "1") (pinfunction "1_1") (pintype "passive"))
    )
    (net (code "74") (name "Net-(LED4-Pad3)") (class "Default")
      (node (ref "LED4") (pin "3") (pinfunction "3_3") (pintype "power_in"))
      (node (ref "R67") (pin "1") (pinfunction "1_1") (pintype "passive"))
    )
    (net (code "75") (name "Net-(LED4-Pad4)") (class "Default")
      (node (ref "LED4") (pin "4") (pinfunction "4_4") (pintype "power_in"))
      (node (ref "R68") (pin "1") (pinfunction "1_1") (pintype "passive"))
    )
    (net (code "76") (name "Net-(LED5-Pad3)") (class "Default")
      (node (ref "LED5") (pin "3") (pinfunction "3_3") (pintype "power_in"))
      (node (ref "R70") (pin "1") (pinfunction "1_1") (pintype "passive"))
    )
    (net (code "77") (name "Net-(LED5-Pad4)") (class "Default")
      (node (ref "LED5") (pin "4") (pinfunction "4_4") (pintype "power_in"))
      (node (ref "R72") (pin "1") (pinfunction "1_1") (pintype "passive"))
    )
    (net (code "78") (name "Net-(LED6-Pad1)") (class "Default")
      (node (ref "LED6") (pin "1") (pinfunction "1_1") (pintype "power_in"))
      (node (ref "R74") (pin "2") (pinfunction "2_2") (pintype "passive"))
    )
    (net (code "79") (name "Net-(LS1-Pad2)") (class "Default")
      (node (ref "LS1") (pin "2") (pinfunction "2_2") (pintype "passive"))
      (node (ref "R71") (pin "2") (pinfunction "2_2") (pintype "passive"))
      (node (ref "VT2") (pin "D") (pinfunction "D_D") (pintype "passive"))
    )
    (net (code "80") (name "Net-(R44-Pad1)") (class "Default")
      (node (ref "R44") (pin "1") (pinfunction "1_1") (pintype "passive"))
      (node (ref "R47") (pin "2") (pinfunction "2_2") (pintype "passive"))
      (node (ref "R50") (pin "1") (pinfunction "1_1") (pintype "passive"))
    )
    (net (code "81") (name "VCC1P8") (class "Default")
      (node (ref "R43") (pin "2") (pinfunction "2_2") (pintype "passive"))
      (node (ref "R69") (pin "1") (pinfunction "1_1") (pintype "passive"))
    )
    (net (code "82") (name "VCC3P0_BATT") (class "Default")
      (node (ref "J6") (pin "2") (pinfunction "2_2") (pintype "passive"))
      (node (ref "R53") (pin "2") (pinfunction "2_2") (pintype "passive"))
    )
    (net (code "83") (name "VCC3P3") (class "Default")
      (node (ref "C135") (pin "1") (pinfunction "1_1") (pintype "passive"))
      (node (ref "C137") (pin "2") (pinfunction "2_2") (pintype "passive"))
      (node (ref "C141") (pin "1") (pinfunction "1_1") (pintype "passive"))
      (node (ref "C142") (pin "2") (pinfunction "2_2") (pintype "passive"))
      (node (ref "C144") (pin "2") (pinfunction "2_2") (pintype "passive"))
      (node (ref "C145") (pin "1") (pinfunction "1_1") (pintype "passive"))
      (node (ref "C146") (pin "2") (pinfunction "2_2") (pintype "passive"))
      (node (ref "C148") (pin "1") (pinfunction "1_1") (pintype "passive"))
      (node (ref "IC13") (pin "8") (pinfunction "VCC_8") (pintype "passive"))
      (node (ref "IC15") (pin "10") (pinfunction "~{MR}_10") (pintype "input"))
      (node (ref "IC15") (pin "16") (pinfunction "VCC_16") (pintype "power_in"))
      (node (ref "IC16") (pin "8") (pinfunction "VCC_8") (pintype "power_in"))
      (node (ref "IC17") (pin "10") (pinfunction "~{MR}_10") (pintype "input"))
      (node (ref "IC17") (pin "16") (pinfunction "VCC_16") (pintype "power_in"))
      (node (ref "IC18") (pin "8") (pinfunction "VCC_8") (pintype "passive"))
      (node (ref "IC19") (pin "10") (pinfunction "~{MR}_10") (pintype "input"))
      (node (ref "IC19") (pin "16") (pinfunction "VCC_16") (pintype "power_in"))
      (node (ref "IC20") (pin "8") (pinfunction "VCC_8") (pintype "power_in"))
      (node (ref "IC21") (pin "8") (pinfunction "VCC_8") (pintype "power_in"))
      (node (ref "IC22") (pin "10") (pinfunction "~{MR}_10") (pintype "input"))
      (node (ref "IC22") (pin "16") (pinfunction "VCC_16") (pintype "power_in"))
      (node (ref "IC23") (pin "8") (pinfunction "VCC_8") (pintype "passive"))
      (node (ref "LED1") (pin "1") (pinfunction "1_1") (pintype "power_in"))
      (node (ref "LED1") (pin "2") (pinfunction "2_2") (pintype "power_in"))
      (node (ref "LED2") (pin "1") (pinfunction "1_1") (pintype "power_in"))
      (node (ref "LED2") (pin "2") (pinfunction "2_2") (pintype "power_in"))
      (node (ref "LED3") (pin "1") (pinfunction "1_1") (pintype "power_in"))
      (node (ref "LED3") (pin "2") (pinfunction "2_2") (pintype "power_in"))
      (node (ref "LED4") (pin "1") (pinfunction "1_1") (pintype "power_in"))
      (node (ref "LED4") (pin "2") (pinfunction "2_2") (pintype "power_in"))
      (node (ref "LED5") (pin "1") (pinfunction "1_1") (pintype "power_in"))
      (node (ref "LED5") (pin "2") (pinfunction "2_2") (pintype "power_in"))
      (node (ref "LS1") (pin "1") (pinfunction "1_1") (pintype "passive"))
      (node (ref "R45") (pin "1") (pinfunction "1_1") (pintype "passive"))
      (node (ref "R48") (pin "1") (pinfunction "1_1") (pintype "passive"))
      (node (ref "R59") (pin "1") (pinfunction "1_1") (pintype "passive"))
      (node (ref "R74") (pin "1") (pinfunction "1_1") (pintype "passive"))
      (node (ref "R75") (pin "1") (pinfunction "1_1") (pintype "passive"))
      (node (ref "R76") (pin "1") (pinfunction "1_1") (pintype "passive"))
    )
    (net (code "84") (name "VCC3P3_CLK") (class "Default")
      (node (ref "FR36") (pin "1") (pinfunction "1_1") (pintype "passive"))
    )
    (net (code "85") (name "VCC3P3_GNSS") (class "Default")
      (node (ref "C132") (pin "2") (pinfunction "2_2") (pintype "passive"))
      (node (ref "C133") (pin "2") (pinfunction "2_2") (pintype "passive"))
      (node (ref "C139") (pin "2") (pinfunction "2_2") (pintype "passive"))
      (node (ref "C140") (pin "1") (pinfunction "1_1") (pintype "passive"))
      (node (ref "FR36") (pin "2") (pinfunction "2_2") (pintype "passive"))
      (node (ref "IC14") (pin "23") (pinfunction "VCC_23") (pintype "passive"))
      (node (ref "R46") (pin "2") (pinfunction "2_2") (pintype "passive"))
      (node (ref "R47") (pin "1") (pinfunction "1_1") (pintype "passive"))
      (node (ref "R54") (pin "2") (pinfunction "2_2") (pintype "passive"))
    )
    (net (code "86") (name "VCC5P0") (class "Default")
      (node (ref "R61") (pin "1") (pinfunction "1_1") (pintype "passive"))
    )
    (net (code "87") (name "unconnected-(IC14-DDC_SCL{slash}SPI_CLK-Pad19)") (class "Default")
      (node (ref "IC14") (pin "19") (pinfunction "DDC_SCL/SPI_CLK_19") (pintype "passive+no_connect"))
    )
    (net (code "88") (name "unconnected-(IC14-DDC_SDA{slash}SPI_CSN-Pad18)") (class "Default")
      (node (ref "IC14") (pin "18") (pinfunction "DDC_SDA/SPI_CSN_18") (pintype "passive+no_connect"))
    )
    (net (code "89") (name "unconnected-(IC14-EXTINT-Pad4)") (class "Default")
      (node (ref "IC14") (pin "4") (pinfunction "EXTINT_4") (pintype "passive+no_connect"))
    )
    (net (code "90") (name "unconnected-(IC14-GEOFENCE_STAT{slash}RESV-Pad16)") (class "Default")
      (node (ref "IC14") (pin "16") (pinfunction "GEOFENCE_STAT/RESV_16") (pintype "passive+no_connect"))
    )
    (net (code "91") (name "unconnected-(IC14-LNA_EN{slash}RESV-Pad14)") (class "Default")
      (node (ref "IC14") (pin "14") (pinfunction "LNA_EN/RESV_14") (pintype "passive+no_connect"))
    )
    (net (code "92") (name "unconnected-(IC14-RESET_N-Pad8)") (class "Default")
      (node (ref "IC14") (pin "8") (pinfunction "RESET_N_8") (pintype "passive+no_connect"))
    )
    (net (code "93") (name "unconnected-(IC14-RESV-Pad17)") (class "Default")
      (node (ref "IC14") (pin "17") (pinfunction "RESV_17") (pintype "passive+no_connect"))
    )
    (net (code "94") (name "unconnected-(IC14-RTK_STAT{slash}RESV-Pad15)") (class "Default")
      (node (ref "IC14") (pin "15") (pinfunction "RTK_STAT/RESV_15") (pintype "passive+no_connect"))
    )
    (net (code "95") (name "unconnected-(IC19-Q7-Pad7)") (class "Default")
      (node (ref "IC19") (pin "7") (pinfunction "Q7_7") (pintype "output+no_connect"))
    )
    (net (code "96") (name "unconnected-(IC20-NC-Pad1)") (class "Default")
      (node (ref "IC20") (pin "1") (pinfunction "NC_1") (pintype "passive+no_connect"))
    )
    (net (code "97") (name "unconnected-(IC20-NC-Pad2)") (class "Default")
      (node (ref "IC20") (pin "2") (pinfunction "NC_2") (pintype "passive+no_connect"))
    )
    (net (code "98") (name "unconnected-(IC20-NC-Pad3)") (class "Default")
      (node (ref "IC20") (pin "3") (pinfunction "NC_3") (pintype "passive+no_connect"))
    )
    (net (code "99") (name "unconnected-(IC20-NC-Pad7)") (class "Default")
      (node (ref "IC20") (pin "7") (pinfunction "NC_7") (pintype "passive+no_connect"))
    )
    (net (code "100") (name "unconnected-(IC21-NC-Pad1)") (class "Default")
      (node (ref "IC21") (pin "1") (pinfunction "NC_1") (pintype "passive+no_connect"))
    )
    (net (code "101") (name "unconnected-(IC21-NC-Pad2)") (class "Default")
      (node (ref "IC21") (pin "2") (pinfunction "NC_2") (pintype "passive+no_connect"))
    )
    (net (code "102") (name "unconnected-(IC21-NC-Pad3)") (class "Default")
      (node (ref "IC21") (pin "3") (pinfunction "NC_3") (pintype "passive+no_connect"))
    )
    (net (code "103") (name "unconnected-(IC21-NC-Pad7)") (class "Default")
      (node (ref "IC21") (pin "7") (pinfunction "NC_7") (pintype "passive+no_connect"))
    )
    (net (code "104") (name "unconnected-(LED6-Pad2)") (class "Default")
      (node (ref "LED6") (pin "2") (pinfunction "2_2") (pintype "power_in+no_connect"))
    )
    (net (code "105") (name "unconnected-(LED6-Pad4)") (class "Default")
      (node (ref "LED6") (pin "4") (pinfunction "4_4") (pintype "power_in+no_connect"))
    )
  )
)
